# DASS01_CV_Amp.net
KiCad netlist of a schematic drawn in EAGLE
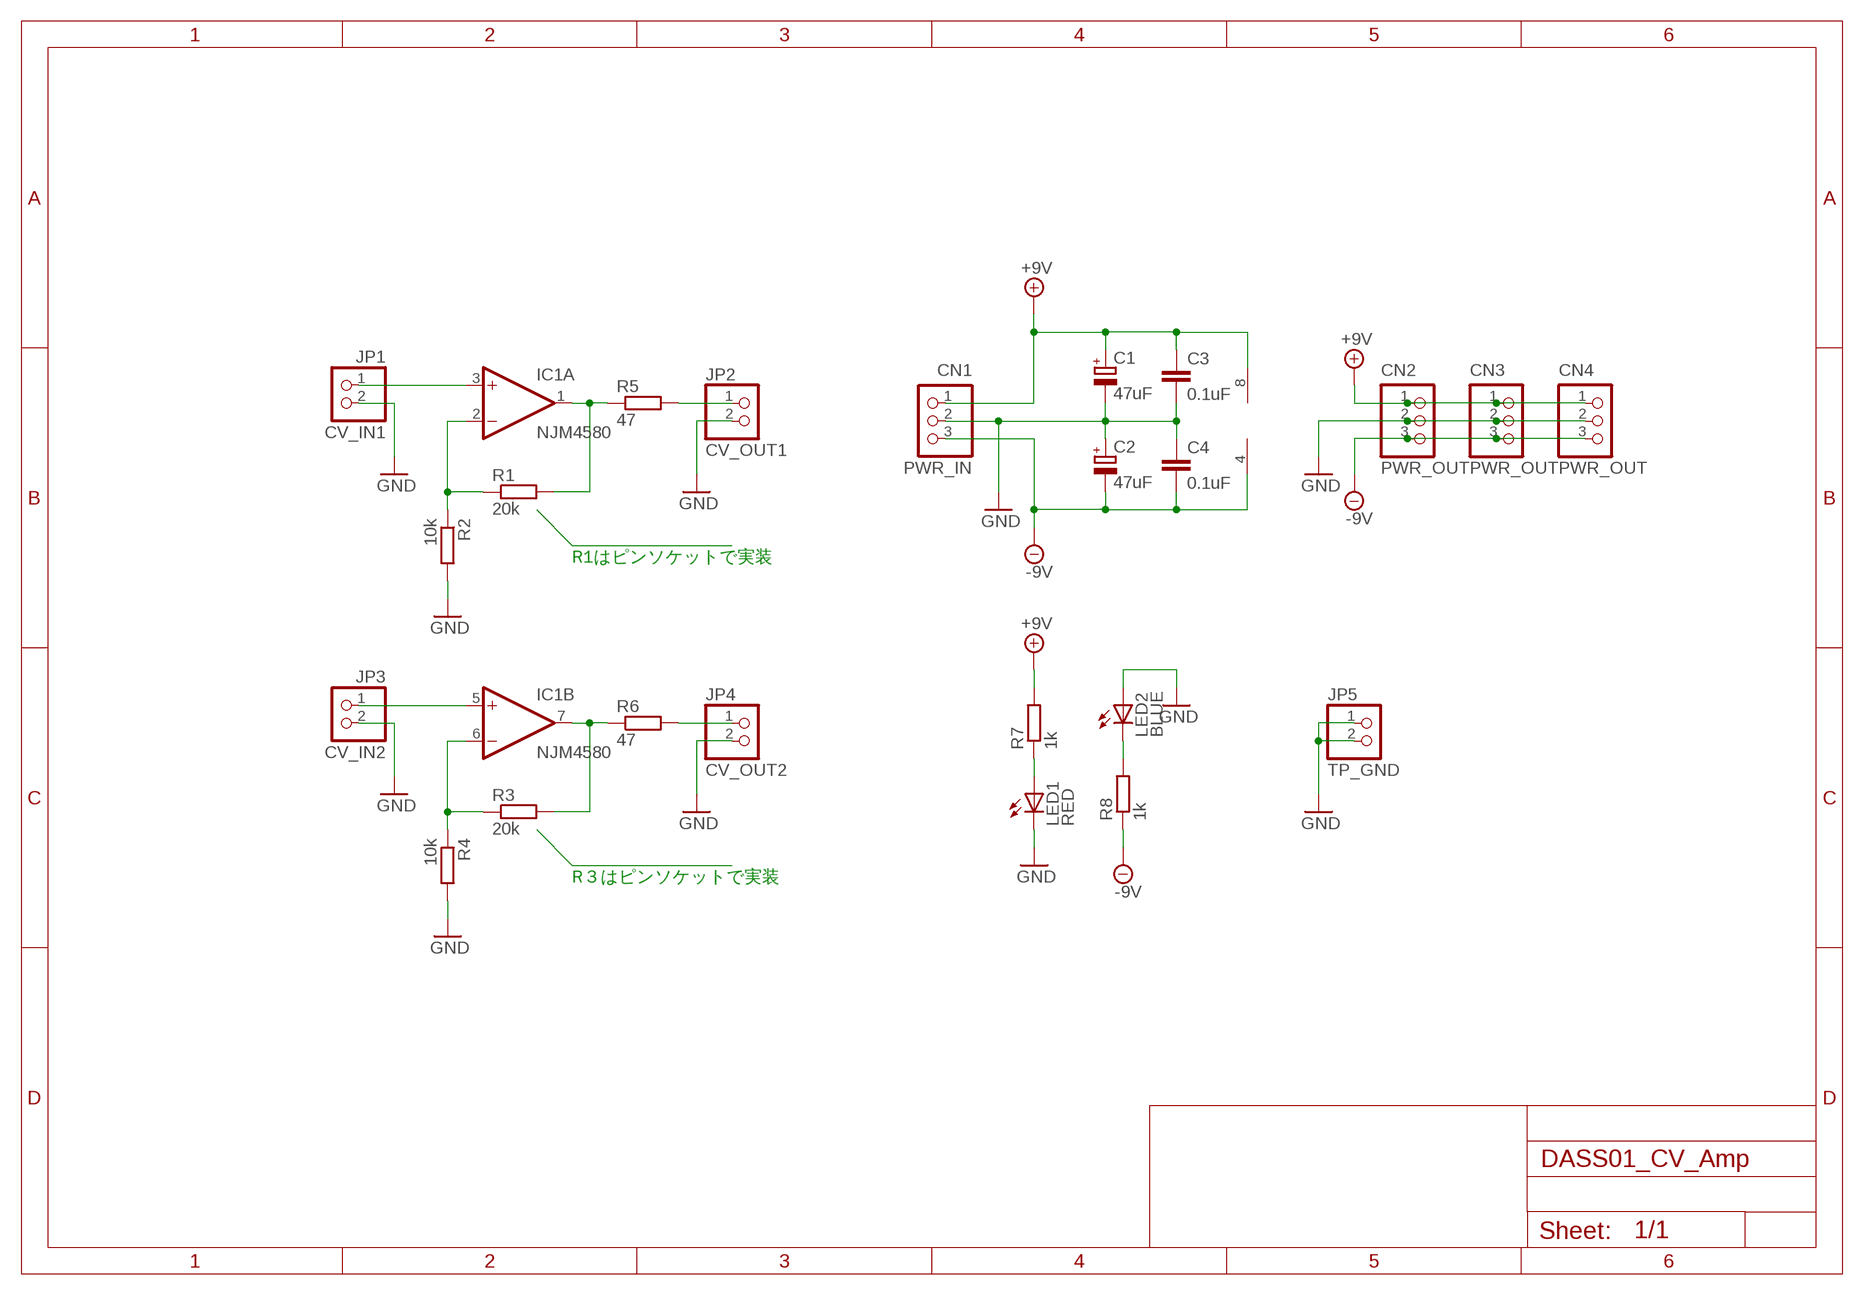
[diagram p0: schematic, sheet 1]

(export (version "E")
  (design (tool "Eeschema 10.0.6"))
  (components
    (comp (ref "C1")
      (value "47uF")
      (footprint "eagle-import:E2,5-7")
      (libsource (lib "eagle-import") (part "CPOL-EUE2.5-7"))
    )
    (comp (ref "C2")
      (value "47uF")
      (footprint "eagle-import:E2,5-7")
      (libsource (lib "eagle-import") (part "CPOL-EUE2.5-7"))
    )
    (comp (ref "C3")
      (value "0.1uF")
      (footprint "eagle-import:C025-024X044")
      (libsource (lib "eagle-import") (part "C-EU025-024X044"))
    )
    (comp (ref "C4")
      (value "0.1uF")
      (footprint "eagle-import:C025-024X044")
      (libsource (lib "eagle-import") (part "C-EU025-024X044"))
    )
    (comp (ref "CN1")
      (value "PWR_IN")
      (footprint "eagle-import:B3B-XH-A")
      (libsource (lib "eagle-import") (part "B3B-XH-A"))
    )
    (comp (ref "CN2")
      (value "PWR_OUT")
      (footprint "eagle-import:B3B-XH-A")
      (libsource (lib "eagle-import") (part "B3B-XH-A"))
    )
    (comp (ref "CN3")
      (value "PWR_OUT")
      (footprint "eagle-import:B3B-XH-A")
      (libsource (lib "eagle-import") (part "B3B-XH-A"))
    )
    (comp (ref "CN4")
      (value "PWR_OUT")
      (footprint "eagle-import:B3B-XH-A")
      (libsource (lib "eagle-import") (part "B3B-XH-A"))
    )
    (comp (ref "IC1")
      (value "NJM4580")
      (footprint "eagle-import:DIL08")
      (libsource (lib "eagle-import") (part "RC4559N"))
    )
    (comp (ref "JP1")
      (value "CV_IN1")
      (footprint "eagle-import:1X02")
      (libsource (lib "eagle-import") (part "PINHD-1X2"))
    )
    (comp (ref "JP2")
      (value "CV_OUT1")
      (footprint "eagle-import:1X02")
      (libsource (lib "eagle-import") (part "PINHD-1X2"))
    )
    (comp (ref "JP3")
      (value "CV_IN2")
      (footprint "eagle-import:1X02")
      (libsource (lib "eagle-import") (part "PINHD-1X2"))
    )
    (comp (ref "JP4")
      (value "CV_OUT2")
      (footprint "eagle-import:1X02")
      (libsource (lib "eagle-import") (part "PINHD-1X2"))
    )
    (comp (ref "JP5")
      (value "TP_GND")
      (footprint "eagle-import:1X02")
      (libsource (lib "eagle-import") (part "PINHD-1X2"))
    )
    (comp (ref "LED1")
      (value "RED")
      (footprint "eagle-import:LED3MM")
      (libsource (lib "eagle-import") (part "LED3MM"))
    )
    (comp (ref "LED2")
      (value "BLUE")
      (footprint "eagle-import:LED3MM")
      (libsource (lib "eagle-import") (part "LED3MM"))
    )
    (comp (ref "R1")
      (value "20k")
      (footprint "eagle-import:0207_7")
      (libsource (lib "eagle-import") (part "R-EU_0207/7"))
    )
    (comp (ref "R2")
      (value "10k")
      (footprint "eagle-import:0207_7")
      (libsource (lib "eagle-import") (part "R-EU_0207/7"))
    )
    (comp (ref "R3")
      (value "20k")
      (footprint "eagle-import:0207_7")
      (libsource (lib "eagle-import") (part "R-EU_0207/7"))
    )
    (comp (ref "R4")
      (value "10k")
      (footprint "eagle-import:0207_7")
      (libsource (lib "eagle-import") (part "R-EU_0207/7"))
    )
    (comp (ref "R5")
      (value "47")
      (footprint "eagle-import:0207_7")
      (libsource (lib "eagle-import") (part "R-EU_0207/7"))
    )
    (comp (ref "R6")
      (value "47")
      (footprint "eagle-import:0207_7")
      (libsource (lib "eagle-import") (part "R-EU_0207/7"))
    )
    (comp (ref "R7")
      (value "1k")
      (footprint "eagle-import:0207_7")
      (libsource (lib "eagle-import") (part "R-EU_0207/7"))
    )
    (comp (ref "R8")
      (value "1k")
      (footprint "eagle-import:0207_7")
      (libsource (lib "eagle-import") (part "R-EU_0207/7"))
    )
  )
  (nets
    (net (code "1") (name "+9V") (class "Default")
      (node (ref "C1") (pin "+") (pinfunction "+_+") (pintype "passive"))
      (node (ref "C3") (pin "1") (pinfunction "1_1") (pintype "passive"))
      (node (ref "CN1") (pin "1") (pinfunction "1_1") (pintype "passive"))
      (node (ref "CN2") (pin "1") (pinfunction "1_1") (pintype "passive"))
      (node (ref "CN3") (pin "1") (pinfunction "1_1") (pintype "passive"))
      (node (ref "CN4") (pin "1") (pinfunction "1_1") (pintype "passive"))
      (node (ref "IC1") (pin "8") (pinfunction "V+_8") (pintype "power_in"))
      (node (ref "R7") (pin "2") (pinfunction "2_2") (pintype "passive"))
    )
    (net (code "2") (name "-9V") (class "Default")
      (node (ref "C2") (pin "-") (pinfunction "-_-") (pintype "passive"))
      (node (ref "C4") (pin "2") (pinfunction "2_2") (pintype "passive"))
      (node (ref "CN1") (pin "3") (pinfunction "3_3") (pintype "passive"))
      (node (ref "CN2") (pin "3") (pinfunction "3_3") (pintype "passive"))
      (node (ref "CN3") (pin "3") (pinfunction "3_3") (pintype "passive"))
      (node (ref "CN4") (pin "3") (pinfunction "3_3") (pintype "passive"))
      (node (ref "IC1") (pin "4") (pinfunction "V-_4") (pintype "power_in"))
      (node (ref "R8") (pin "1") (pinfunction "1_1") (pintype "passive"))
    )
    (net (code "3") (name "GND") (class "Default")
      (node (ref "C1") (pin "-") (pinfunction "-_-") (pintype "passive"))
      (node (ref "C2") (pin "+") (pinfunction "+_+") (pintype "passive"))
      (node (ref "C3") (pin "2") (pinfunction "2_2") (pintype "passive"))
      (node (ref "C4") (pin "1") (pinfunction "1_1") (pintype "passive"))
      (node (ref "CN1") (pin "2") (pinfunction "2_2") (pintype "passive"))
      (node (ref "CN2") (pin "2") (pinfunction "2_2") (pintype "passive"))
      (node (ref "CN3") (pin "2") (pinfunction "2_2") (pintype "passive"))
      (node (ref "CN4") (pin "2") (pinfunction "2_2") (pintype "passive"))
      (node (ref "JP1") (pin "2") (pinfunction "2_2") (pintype "passive"))
      (node (ref "JP2") (pin "2") (pinfunction "2_2") (pintype "passive"))
      (node (ref "JP3") (pin "2") (pinfunction "2_2") (pintype "passive"))
      (node (ref "JP4") (pin "2") (pinfunction "2_2") (pintype "passive"))
      (node (ref "JP5") (pin "1") (pinfunction "1_1") (pintype "passive"))
      (node (ref "JP5") (pin "2") (pinfunction "2_2") (pintype "passive"))
      (node (ref "LED1") (pin "K") (pinfunction "C_K") (pintype "passive"))
      (node (ref "LED2") (pin "A") (pinfunction "A_A") (pintype "passive"))
      (node (ref "R2") (pin "2") (pinfunction "2_2") (pintype "passive"))
      (node (ref "R4") (pin "2") (pinfunction "2_2") (pintype "passive"))
    )
    (net (code "4") (name "Net-(IC1A-+IN)") (class "Default")
      (node (ref "IC1") (pin "3") (pinfunction "+IN_3") (pintype "input"))
      (node (ref "JP1") (pin "1") (pinfunction "1_1") (pintype "passive"))
    )
    (net (code "5") (name "Net-(IC1A--IN)") (class "Default")
      (node (ref "IC1") (pin "2") (pinfunction "-IN_2") (pintype "input"))
      (node (ref "R1") (pin "1") (pinfunction "1_1") (pintype "passive"))
      (node (ref "R2") (pin "1") (pinfunction "1_1") (pintype "passive"))
    )
    (net (code "6") (name "Net-(IC1A-OUT)") (class "Default")
      (node (ref "IC1") (pin "1") (pinfunction "OUT_1") (pintype "output"))
      (node (ref "R1") (pin "2") (pinfunction "2_2") (pintype "passive"))
      (node (ref "R5") (pin "1") (pinfunction "1_1") (pintype "passive"))
    )
    (net (code "7") (name "Net-(IC1B-+IN)") (class "Default")
      (node (ref "IC1") (pin "5") (pinfunction "+IN_5") (pintype "input"))
      (node (ref "JP3") (pin "1") (pinfunction "1_1") (pintype "passive"))
    )
    (net (code "8") (name "Net-(IC1B--IN)") (class "Default")
      (node (ref "IC1") (pin "6") (pinfunction "-IN_6") (pintype "input"))
      (node (ref "R3") (pin "1") (pinfunction "1_1") (pintype "passive"))
      (node (ref "R4") (pin "1") (pinfunction "1_1") (pintype "passive"))
    )
    (net (code "9") (name "Net-(IC1B-OUT)") (class "Default")
      (node (ref "IC1") (pin "7") (pinfunction "OUT_7") (pintype "output"))
      (node (ref "R3") (pin "2") (pinfunction "2_2") (pintype "passive"))
      (node (ref "R6") (pin "1") (pinfunction "1_1") (pintype "passive"))
    )
    (net (code "10") (name "Net-(JP2-Pad1)") (class "Default")
      (node (ref "JP2") (pin "1") (pinfunction "1_1") (pintype "passive"))
      (node (ref "R5") (pin "2") (pinfunction "2_2") (pintype "passive"))
    )
    (net (code "11") (name "Net-(JP4-Pad1)") (class "Default")
      (node (ref "JP4") (pin "1") (pinfunction "1_1") (pintype "passive"))
      (node (ref "R6") (pin "2") (pinfunction "2_2") (pintype "passive"))
    )
    (net (code "12") (name "Net-(LED1-PadA)") (class "Default")
      (node (ref "LED1") (pin "A") (pinfunction "A_A") (pintype "passive"))
      (node (ref "R7") (pin "1") (pinfunction "1_1") (pintype "passive"))
    )
    (net (code "13") (name "Net-(LED2-C)") (class "Default")
      (node (ref "LED2") (pin "K") (pinfunction "C_K") (pintype "passive"))
      (node (ref "R8") (pin "2") (pinfunction "2_2") (pintype "passive"))
    )
  )
)
